# Arduino.net
KiCad netlist of a schematic drawn in EAGLE
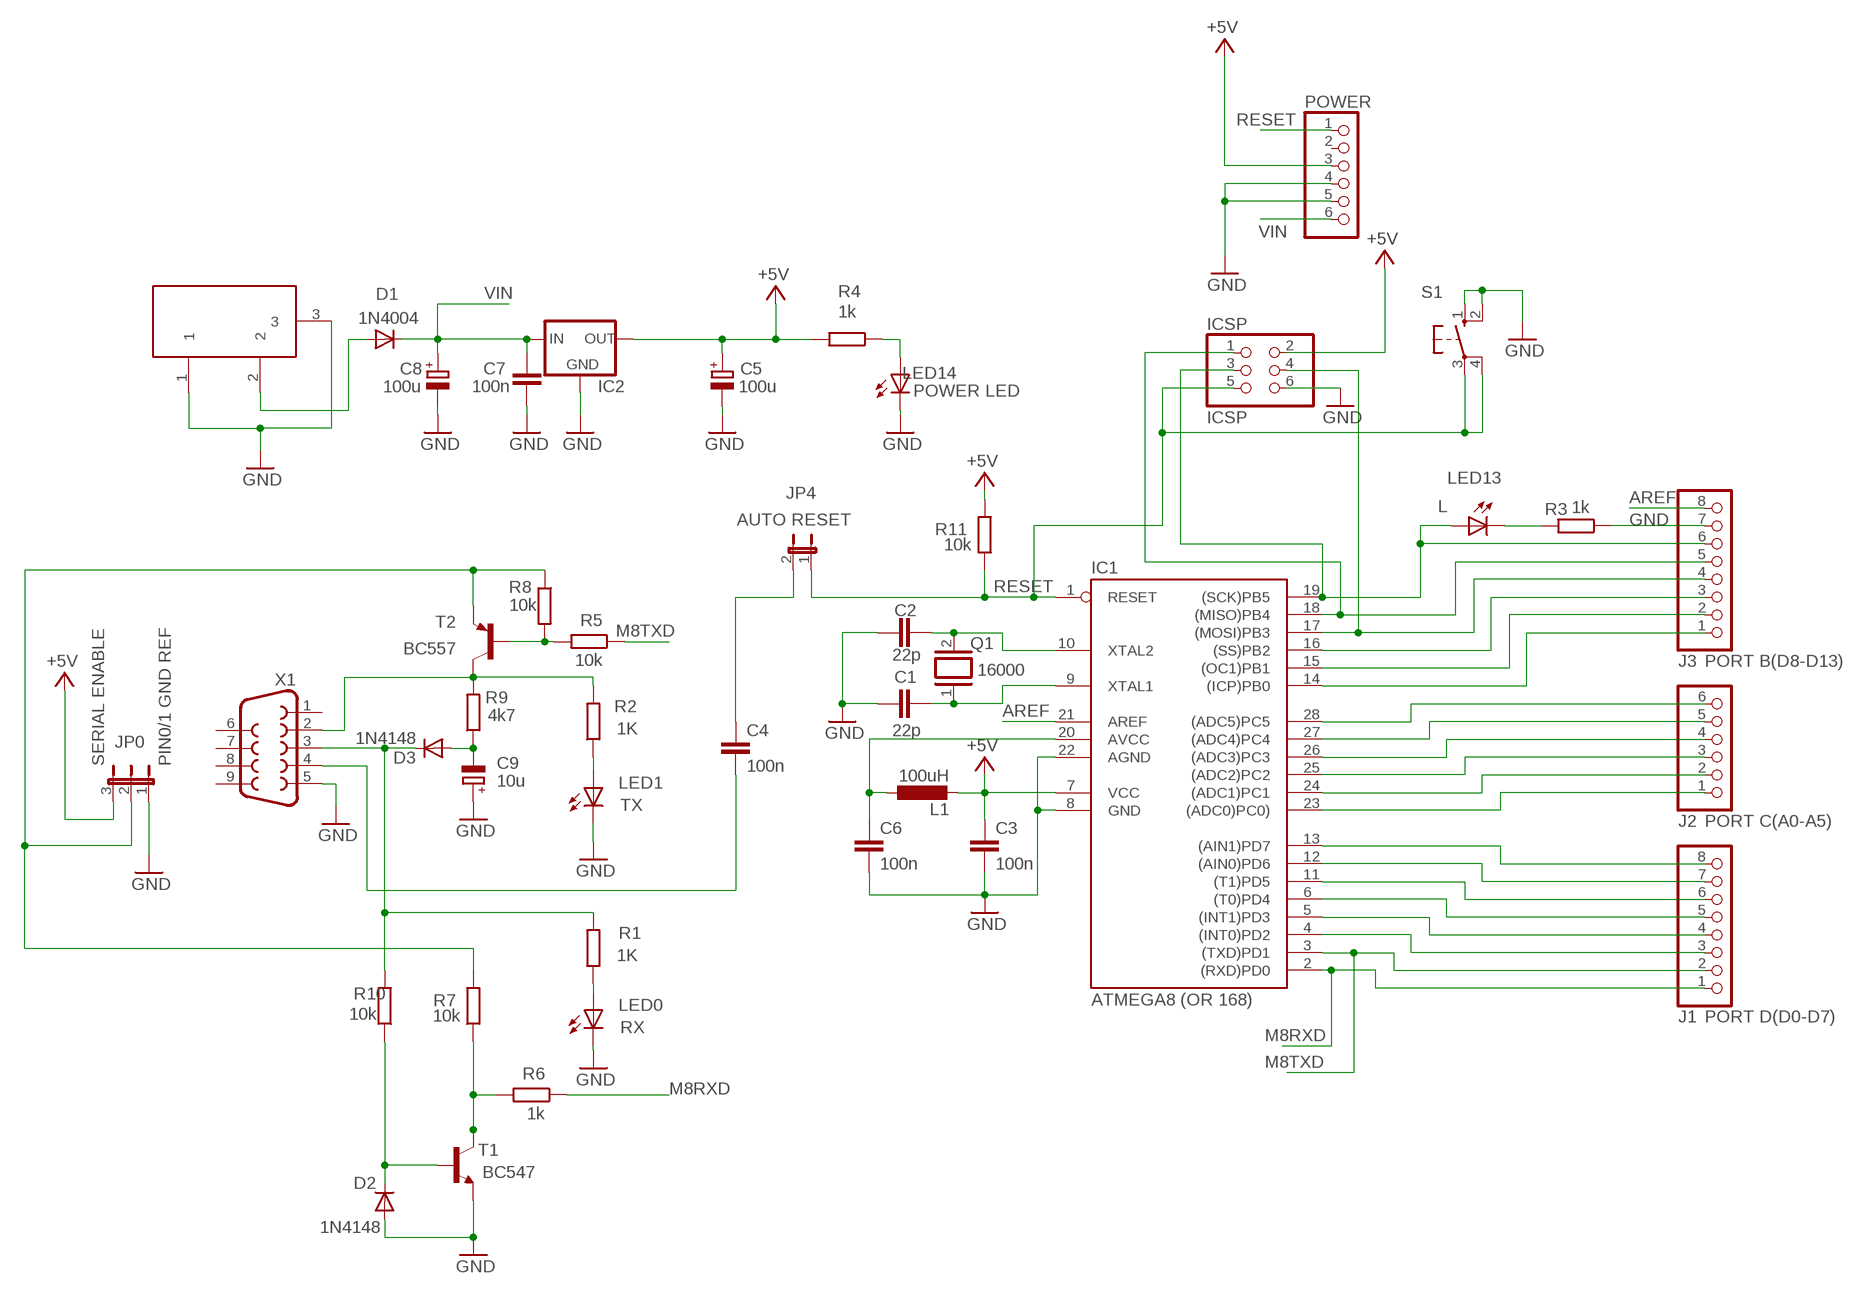
[diagram p0: schematic, sheet 1]

(export (version "E")
  (design (tool "Eeschema 10.0.6"))
  (components
    (comp (ref "C1")
      (value "22p")
      (footprint "eagle-import:C050-025X075")
      (libsource (lib "eagle-import") (part "C-EU050-025X075"))
    )
    (comp (ref "C2")
      (value "22p")
      (footprint "eagle-import:C050-025X075")
      (libsource (lib "eagle-import") (part "C-EU050-025X075"))
    )
    (comp (ref "C3")
      (value "100n")
      (footprint "eagle-import:C050-025X075")
      (libsource (lib "eagle-import") (part "C-EU050-025X075"))
    )
    (comp (ref "C4")
      (value "100n")
      (footprint "eagle-import:C050-025X075")
      (libsource (lib "eagle-import") (part "C-EU050-025X075"))
    )
    (comp (ref "C5")
      (value "100u")
      (footprint "eagle-import:E3,5-8")
      (libsource (lib "eagle-import") (part "CPOL-EUE3.5-8"))
    )
    (comp (ref "C6")
      (value "100n")
      (footprint "eagle-import:C050-025X075")
      (libsource (lib "eagle-import") (part "C-EU050-025X075"))
    )
    (comp (ref "C7")
      (value "100n")
      (footprint "eagle-import:C050-025X075")
      (libsource (lib "eagle-import") (part "C-EU050-025X075"))
    )
    (comp (ref "C8")
      (value "100u")
      (footprint "eagle-import:E3,5-8")
      (libsource (lib "eagle-import") (part "CPOL-EUE3.5-8"))
    )
    (comp (ref "C9")
      (value "10u")
      (footprint "eagle-import:E5-6")
      (libsource (lib "eagle-import") (part "CPOL-EUE5-6"))
    )
    (comp (ref "D1")
      (value "1N4004")
      (footprint "eagle-import:DO41-10")
      (libsource (lib "eagle-import") (part "1N4004"))
    )
    (comp (ref "D2")
      (value "1N4148")
      (footprint "eagle-import:DO35-10")
      (libsource (lib "eagle-import") (part "1N4148"))
    )
    (comp (ref "D3")
      (value "1N4148")
      (footprint "eagle-import:DO35-10")
      (libsource (lib "eagle-import") (part "1N4148"))
    )
    (comp (ref "DC1")
      (value "DC21MMX")
      (footprint "eagle-import:DC-21MM")
      (libsource (lib "eagle-import") (part "DC21MMX"))
    )
    (comp (ref "IC1")
      (value "ATMEGA8 (OR 168)")
      (footprint "eagle-import:DIL28-3")
      (libsource (lib "eagle-import") (part "AT90S4433P"))
    )
    (comp (ref "IC2")
      (value "78XXL")
      (footprint "eagle-import:78XXL")
      (libsource (lib "eagle-import") (part "78XXL"))
    )
    (comp (ref "ICSP")
      (value "ICSP")
      (footprint "eagle-import:2X03")
      (libsource (lib "eagle-import") (part "PINHD-2X3"))
    )
    (comp (ref "J1")
      (value "PORT D(D0-D7)")
      (footprint "eagle-import:1X08")
      (libsource (lib "eagle-import") (part "PINHD-1X8"))
    )
    (comp (ref "J2")
      (value "PORT C(A0-A5)")
      (footprint "eagle-import:1X06")
      (libsource (lib "eagle-import") (part "PINHD-1X6"))
    )
    (comp (ref "J3")
      (value "PORT B(D8-D13)")
      (footprint "eagle-import:1X08")
      (libsource (lib "eagle-import") (part "PINHD-1X8"))
    )
    (comp (ref "JP0")
      (value "JP2W")
      (footprint "eagle-import:JP2W")
      (libsource (lib "eagle-import") (part "JP2W"))
    )
    (comp (ref "JP4")
      (value "AUTO RESET")
      (footprint "eagle-import:JP1W")
      (libsource (lib "eagle-import") (part "JP1W"))
    )
    (comp (ref "L1")
      (value "100uH")
      (footprint "eagle-import:0207_10")
      (libsource (lib "eagle-import") (part "L-EU0207/10"))
    )
    (comp (ref "LED0")
      (value "RX")
      (footprint "eagle-import:LED3MM")
      (libsource (lib "eagle-import") (part "LED3MM"))
    )
    (comp (ref "LED1")
      (value "TX")
      (footprint "eagle-import:LED3MM")
      (libsource (lib "eagle-import") (part "LED3MM"))
    )
    (comp (ref "LED13")
      (value "L")
      (footprint "eagle-import:LED3MM")
      (libsource (lib "eagle-import") (part "LED3MM"))
    )
    (comp (ref "LED14")
      (value "POWER LED")
      (footprint "eagle-import:LED3MM")
      (libsource (lib "eagle-import") (part "LED3MM"))
    )
    (comp (ref "POWER")
      (value "PINHD-1X6")
      (footprint "eagle-import:1X06")
      (libsource (lib "eagle-import") (part "PINHD-1X6"))
    )
    (comp (ref "Q1")
      (value "16000")
      (footprint "eagle-import:Q")
      (libsource (lib "eagle-import") (part "XTAL"))
    )
    (comp (ref "R1")
      (value "1K")
      (footprint "eagle-import:0207_10")
      (libsource (lib "eagle-import") (part "R-EU_0207/10"))
    )
    (comp (ref "R2")
      (value "1K")
      (footprint "eagle-import:0207_10")
      (libsource (lib "eagle-import") (part "R-EU_0207/10"))
    )
    (comp (ref "R3")
      (value "1k")
      (footprint "eagle-import:0207_10")
      (libsource (lib "eagle-import") (part "R-EU_0207/10"))
    )
    (comp (ref "R4")
      (value "1k")
      (footprint "eagle-import:0207_10")
      (libsource (lib "eagle-import") (part "R-EU_0207/10"))
    )
    (comp (ref "R5")
      (value "10k")
      (footprint "eagle-import:0207_10")
      (libsource (lib "eagle-import") (part "R-EU_0207/10"))
    )
    (comp (ref "R6")
      (value "1k")
      (footprint "eagle-import:0207_10")
      (libsource (lib "eagle-import") (part "R-EU_0207/10"))
    )
    (comp (ref "R7")
      (value "10k")
      (footprint "eagle-import:0207_10")
      (libsource (lib "eagle-import") (part "R-EU_0207/10"))
    )
    (comp (ref "R8")
      (value "10k")
      (footprint "eagle-import:0207_10")
      (libsource (lib "eagle-import") (part "R-EU_0207/10"))
    )
    (comp (ref "R9")
      (value "4k7")
      (footprint "eagle-import:0207_10")
      (libsource (lib "eagle-import") (part "R-EU_0207/10"))
    )
    (comp (ref "R10")
      (value "10k")
      (footprint "eagle-import:0207_10")
      (libsource (lib "eagle-import") (part "R-EU_0207/10"))
    )
    (comp (ref "R11")
      (value "10k")
      (footprint "eagle-import:0207_10")
      (libsource (lib "eagle-import") (part "R-EU_0207/10"))
    )
    (comp (ref "S1")
      (value "10-XX")
      (footprint "eagle-import:B3F-10XX")
      (libsource (lib "eagle-import") (part "10-XX"))
    )
    (comp (ref "T1")
      (value "BC547")
      (footprint "eagle-import:TO92")
      (libsource (lib "eagle-import") (part "BC547"))
    )
    (comp (ref "T2")
      (value "BC557")
      (footprint "eagle-import:TO92-EBC")
      (libsource (lib "eagle-import") (part "-PNP-TO92-EBCBC557B"))
    )
    (comp (ref "X1")
      (value "F09H")
      (footprint "eagle-import:F09H")
      (libsource (lib "eagle-import") (part "F09H"))
    )
  )
  (nets
    (net (code "1") (name "+5V") (class "Default")
      (node (ref "C3") (pin "1") (pinfunction "1_1") (pintype "passive"))
      (node (ref "C5") (pin "+") (pinfunction "+_+") (pintype "passive"))
      (node (ref "IC1") (pin "7") (pinfunction "VCC_7") (pintype "power_in"))
      (node (ref "IC2") (pin "OUT") (pinfunction "OUT_OUT") (pintype "passive"))
      (node (ref "ICSP") (pin "2") (pinfunction "2_2") (pintype "passive"))
      (node (ref "JP0") (pin "3") (pinfunction "3_3") (pintype "passive"))
      (node (ref "L1") (pin "2") (pinfunction "2_2") (pintype "passive"))
      (node (ref "POWER") (pin "3") (pinfunction "3_3") (pintype "passive"))
      (node (ref "R11") (pin "2") (pinfunction "2_2") (pintype "passive"))
      (node (ref "R4") (pin "2") (pinfunction "2_2") (pintype "passive"))
    )
    (net (code "2") (name "/AREF") (class "Default")
      (node (ref "IC1") (pin "21") (pinfunction "AREF_21") (pintype "power_in"))
      (node (ref "J3") (pin "8") (pinfunction "8_8") (pintype "passive"))
    )
    (net (code "3") (name "/M8RXD") (class "Default")
      (node (ref "IC1") (pin "2") (pinfunction "(RXD)PD0_2") (pintype "bidirectional"))
      (node (ref "J1") (pin "1") (pinfunction "1_1") (pintype "passive"))
      (node (ref "R6") (pin "1") (pinfunction "1_1") (pintype "passive"))
    )
    (net (code "4") (name "/M8TXD") (class "Default")
      (node (ref "IC1") (pin "3") (pinfunction "(TXD)PD1_3") (pintype "bidirectional"))
      (node (ref "J1") (pin "2") (pinfunction "2_2") (pintype "passive"))
      (node (ref "R5") (pin "1") (pinfunction "1_1") (pintype "passive"))
    )
    (net (code "5") (name "/RESET") (class "Default")
      (node (ref "IC1") (pin "1") (pinfunction "RESET_1") (pintype "input"))
      (node (ref "ICSP") (pin "5") (pinfunction "5_5") (pintype "passive"))
      (node (ref "JP4") (pin "1") (pinfunction "1_1") (pintype "passive"))
      (node (ref "POWER") (pin "1") (pinfunction "1_1") (pintype "passive"))
      (node (ref "R11") (pin "1") (pinfunction "1_1") (pintype "passive"))
      (node (ref "S1") (pin "3") (pinfunction "P_3") (pintype "passive"))
      (node (ref "S1") (pin "4") (pinfunction "P1_4") (pintype "passive"))
    )
    (net (code "6") (name "/VIN") (class "Default")
      (node (ref "C7") (pin "2") (pinfunction "2_2") (pintype "passive"))
      (node (ref "C8") (pin "+") (pinfunction "+_+") (pintype "passive"))
      (node (ref "D1") (pin "C") (pinfunction "C_C") (pintype "passive"))
      (node (ref "IC2") (pin "IN") (pinfunction "IN_IN") (pintype "input"))
      (node (ref "POWER") (pin "6") (pinfunction "6_6") (pintype "passive"))
    )
    (net (code "7") (name "GND") (class "Default")
      (node (ref "C1") (pin "1") (pinfunction "1_1") (pintype "passive"))
      (node (ref "C2") (pin "1") (pinfunction "1_1") (pintype "passive"))
      (node (ref "C3") (pin "2") (pinfunction "2_2") (pintype "passive"))
      (node (ref "C5") (pin "-") (pinfunction "-_-") (pintype "passive"))
      (node (ref "C6") (pin "2") (pinfunction "2_2") (pintype "passive"))
      (node (ref "C7") (pin "1") (pinfunction "1_1") (pintype "passive"))
      (node (ref "C8") (pin "-") (pinfunction "-_-") (pintype "passive"))
      (node (ref "C9") (pin "+") (pinfunction "+_+") (pintype "passive"))
      (node (ref "D2") (pin "A") (pinfunction "A_A") (pintype "passive"))
      (node (ref "DC1") (pin "1") (pinfunction "1_1") (pintype "power_in"))
      (node (ref "DC1") (pin "3") (pinfunction "3_3") (pintype "power_in"))
      (node (ref "IC1") (pin "22") (pinfunction "AGND_22") (pintype "power_in"))
      (node (ref "IC1") (pin "8") (pinfunction "GND_8") (pintype "power_in"))
      (node (ref "IC2") (pin "GND") (pinfunction "GND_GND") (pintype "input"))
      (node (ref "ICSP") (pin "6") (pinfunction "6_6") (pintype "passive"))
      (node (ref "J3") (pin "7") (pinfunction "7_7") (pintype "passive"))
      (node (ref "JP0") (pin "1") (pinfunction "1_1") (pintype "passive"))
      (node (ref "LED0") (pin "K") (pinfunction "C_K") (pintype "passive"))
      (node (ref "LED1") (pin "K") (pinfunction "C_K") (pintype "passive"))
      (node (ref "LED14") (pin "K") (pinfunction "C_K") (pintype "passive"))
      (node (ref "POWER") (pin "4") (pinfunction "4_4") (pintype "passive"))
      (node (ref "POWER") (pin "5") (pinfunction "5_5") (pintype "passive"))
      (node (ref "R3") (pin "1") (pinfunction "1_1") (pintype "passive"))
      (node (ref "S1") (pin "1") (pinfunction "S_1") (pintype "passive"))
      (node (ref "S1") (pin "2") (pinfunction "S1_2") (pintype "passive"))
      (node (ref "T1") (pin "1") (pinfunction "E_1") (pintype "passive"))
      (node (ref "X1") (pin "5") (pinfunction "5_5") (pintype "passive"))
    )
    (net (code "8") (name "Net-(C4-Pad1)") (class "Default")
      (node (ref "C4") (pin "1") (pinfunction "1_1") (pintype "passive"))
      (node (ref "JP4") (pin "2") (pinfunction "2_2") (pintype "passive"))
    )
    (net (code "9") (name "Net-(C4-Pad2)") (class "Default")
      (node (ref "C4") (pin "2") (pinfunction "2_2") (pintype "passive"))
      (node (ref "X1") (pin "4") (pinfunction "4_4") (pintype "passive"))
    )
    (net (code "10") (name "Net-(C9-Pad-)") (class "Default")
      (node (ref "C9") (pin "-") (pinfunction "-_-") (pintype "passive"))
      (node (ref "D3") (pin "A") (pinfunction "A_A") (pintype "passive"))
      (node (ref "R9") (pin "1") (pinfunction "1_1") (pintype "passive"))
    )
    (net (code "11") (name "Net-(D1-PadA)") (class "Default")
      (node (ref "D1") (pin "A") (pinfunction "A_A") (pintype "passive"))
      (node (ref "DC1") (pin "2") (pinfunction "2_2") (pintype "power_in"))
    )
    (net (code "12") (name "Net-(D3-PadC)") (class "Default")
      (node (ref "D3") (pin "C") (pinfunction "C_C") (pintype "passive"))
      (node (ref "R1") (pin "2") (pinfunction "2_2") (pintype "passive"))
      (node (ref "R10") (pin "2") (pinfunction "2_2") (pintype "passive"))
      (node (ref "X1") (pin "3") (pinfunction "3_3") (pintype "passive"))
    )
    (net (code "13") (name "Net-(IC1-(ADC0)PC0))") (class "Default")
      (node (ref "IC1") (pin "23") (pinfunction "(ADC0)PC0)_23") (pintype "bidirectional"))
      (node (ref "J2") (pin "1") (pinfunction "1_1") (pintype "passive"))
    )
    (net (code "14") (name "Net-(IC1-(ADC1)PC1)") (class "Default")
      (node (ref "IC1") (pin "24") (pinfunction "(ADC1)PC1_24") (pintype "bidirectional"))
      (node (ref "J2") (pin "2") (pinfunction "2_2") (pintype "passive"))
    )
    (net (code "15") (name "Net-(IC1-(ADC2)PC2)") (class "Default")
      (node (ref "IC1") (pin "25") (pinfunction "(ADC2)PC2_25") (pintype "bidirectional"))
      (node (ref "J2") (pin "3") (pinfunction "3_3") (pintype "passive"))
    )
    (net (code "16") (name "Net-(IC1-(ADC3)PC3)") (class "Default")
      (node (ref "IC1") (pin "26") (pinfunction "(ADC3)PC3_26") (pintype "bidirectional"))
      (node (ref "J2") (pin "4") (pinfunction "4_4") (pintype "passive"))
    )
    (net (code "17") (name "Net-(IC1-(ADC4)PC4)") (class "Default")
      (node (ref "IC1") (pin "27") (pinfunction "(ADC4)PC4_27") (pintype "bidirectional"))
      (node (ref "J2") (pin "5") (pinfunction "5_5") (pintype "passive"))
    )
    (net (code "18") (name "Net-(IC1-(ADC5)PC5)") (class "Default")
      (node (ref "IC1") (pin "28") (pinfunction "(ADC5)PC5_28") (pintype "bidirectional"))
      (node (ref "J2") (pin "6") (pinfunction "6_6") (pintype "passive"))
    )
    (net (code "19") (name "Net-(IC1-(AIN0)PD6)") (class "Default")
      (node (ref "IC1") (pin "12") (pinfunction "(AIN0)PD6_12") (pintype "bidirectional"))
      (node (ref "J1") (pin "7") (pinfunction "7_7") (pintype "passive"))
    )
    (net (code "20") (name "Net-(IC1-(AIN1)PD7)") (class "Default")
      (node (ref "IC1") (pin "13") (pinfunction "(AIN1)PD7_13") (pintype "bidirectional"))
      (node (ref "J1") (pin "8") (pinfunction "8_8") (pintype "passive"))
    )
    (net (code "21") (name "Net-(IC1-(ICP)PB0)") (class "Default")
      (node (ref "IC1") (pin "14") (pinfunction "(ICP)PB0_14") (pintype "bidirectional"))
      (node (ref "J3") (pin "1") (pinfunction "1_1") (pintype "passive"))
    )
    (net (code "22") (name "Net-(IC1-(INT0)PD2)") (class "Default")
      (node (ref "IC1") (pin "4") (pinfunction "(INT0)PD2_4") (pintype "bidirectional"))
      (node (ref "J1") (pin "3") (pinfunction "3_3") (pintype "passive"))
    )
    (net (code "23") (name "Net-(IC1-(INT1)PD3)") (class "Default")
      (node (ref "IC1") (pin "5") (pinfunction "(INT1)PD3_5") (pintype "bidirectional"))
      (node (ref "J1") (pin "4") (pinfunction "4_4") (pintype "passive"))
    )
    (net (code "24") (name "Net-(IC1-(MISO)PB4)") (class "Default")
      (node (ref "IC1") (pin "18") (pinfunction "(MISO)PB4_18") (pintype "bidirectional"))
      (node (ref "ICSP") (pin "1") (pinfunction "1_1") (pintype "passive"))
      (node (ref "J3") (pin "5") (pinfunction "5_5") (pintype "passive"))
    )
    (net (code "25") (name "Net-(IC1-(MOSI)PB3)") (class "Default")
      (node (ref "IC1") (pin "17") (pinfunction "(MOSI)PB3_17") (pintype "bidirectional"))
      (node (ref "ICSP") (pin "4") (pinfunction "4_4") (pintype "passive"))
      (node (ref "J3") (pin "4") (pinfunction "4_4") (pintype "passive"))
    )
    (net (code "26") (name "Net-(IC1-(OC1)PB1)") (class "Default")
      (node (ref "IC1") (pin "15") (pinfunction "(OC1)PB1_15") (pintype "bidirectional"))
      (node (ref "J3") (pin "2") (pinfunction "2_2") (pintype "passive"))
    )
    (net (code "27") (name "Net-(IC1-(SCK)PB5)") (class "Default")
      (node (ref "IC1") (pin "19") (pinfunction "(SCK)PB5_19") (pintype "bidirectional"))
      (node (ref "ICSP") (pin "3") (pinfunction "3_3") (pintype "passive"))
      (node (ref "J3") (pin "6") (pinfunction "6_6") (pintype "passive"))
      (node (ref "LED13") (pin "A") (pinfunction "A_A") (pintype "passive"))
    )
    (net (code "28") (name "Net-(IC1-(SS)PB2)") (class "Default")
      (node (ref "IC1") (pin "16") (pinfunction "(SS)PB2_16") (pintype "bidirectional"))
      (node (ref "J3") (pin "3") (pinfunction "3_3") (pintype "passive"))
    )
    (net (code "29") (name "Net-(IC1-(T0)PD4)") (class "Default")
      (node (ref "IC1") (pin "6") (pinfunction "(T0)PD4_6") (pintype "bidirectional"))
      (node (ref "J1") (pin "5") (pinfunction "5_5") (pintype "passive"))
    )
    (net (code "30") (name "Net-(IC1-(T1)PD5)") (class "Default")
      (node (ref "IC1") (pin "11") (pinfunction "(T1)PD5_11") (pintype "bidirectional"))
      (node (ref "J1") (pin "6") (pinfunction "6_6") (pintype "passive"))
    )
    (net (code "31") (name "Net-(IC1-AVCC)") (class "Default")
      (node (ref "C6") (pin "1") (pinfunction "1_1") (pintype "passive"))
      (node (ref "IC1") (pin "20") (pinfunction "AVCC_20") (pintype "power_in"))
      (node (ref "L1") (pin "1") (pinfunction "1_1") (pintype "passive"))
    )
    (net (code "32") (name "Net-(IC1-XTAL1)") (class "Default")
      (node (ref "C1") (pin "2") (pinfunction "2_2") (pintype "passive"))
      (node (ref "IC1") (pin "9") (pinfunction "XTAL1_9") (pintype "bidirectional"))
      (node (ref "Q1") (pin "1") (pinfunction "1_1") (pintype "passive"))
    )
    (net (code "33") (name "Net-(IC1-XTAL2)") (class "Default")
      (node (ref "C2") (pin "2") (pinfunction "2_2") (pintype "passive"))
      (node (ref "IC1") (pin "10") (pinfunction "XTAL2_10") (pintype "bidirectional"))
      (node (ref "Q1") (pin "2") (pinfunction "2_2") (pintype "passive"))
    )
    (net (code "34") (name "Net-(JP0-Pad2)") (class "Default")
      (node (ref "JP0") (pin "2") (pinfunction "2_2") (pintype "passive"))
      (node (ref "R7") (pin "2") (pinfunction "2_2") (pintype "passive"))
      (node (ref "R8") (pin "1") (pinfunction "1_1") (pintype "passive"))
      (node (ref "T2") (pin "E") (pinfunction "E_E") (pintype "passive"))
    )
    (net (code "35") (name "Net-(LED0-PadA)") (class "Default")
      (node (ref "LED0") (pin "A") (pinfunction "A_A") (pintype "passive"))
      (node (ref "R1") (pin "1") (pinfunction "1_1") (pintype "passive"))
    )
    (net (code "36") (name "Net-(LED1-PadA)") (class "Default")
      (node (ref "LED1") (pin "A") (pinfunction "A_A") (pintype "passive"))
      (node (ref "R2") (pin "1") (pinfunction "1_1") (pintype "passive"))
    )
    (net (code "37") (name "Net-(LED13-C)") (class "Default")
      (node (ref "LED13") (pin "K") (pinfunction "C_K") (pintype "passive"))
      (node (ref "R3") (pin "2") (pinfunction "2_2") (pintype "passive"))
    )
    (net (code "38") (name "Net-(LED14-PadA)") (class "Default")
      (node (ref "LED14") (pin "A") (pinfunction "A_A") (pintype "passive"))
      (node (ref "R4") (pin "1") (pinfunction "1_1") (pintype "passive"))
    )
    (net (code "39") (name "Net-(R2-Pad2)") (class "Default")
      (node (ref "R2") (pin "2") (pinfunction "2_2") (pintype "passive"))
      (node (ref "R9") (pin "2") (pinfunction "2_2") (pintype "passive"))
      (node (ref "T2") (pin "C") (pinfunction "C_C") (pintype "passive"))
      (node (ref "X1") (pin "2") (pinfunction "2_2") (pintype "passive"))
    )
    (net (code "40") (name "Net-(R5-Pad2)") (class "Default")
      (node (ref "R5") (pin "2") (pinfunction "2_2") (pintype "passive"))
      (node (ref "R8") (pin "2") (pinfunction "2_2") (pintype "passive"))
      (node (ref "T2") (pin "B") (pinfunction "B_B") (pintype "passive"))
    )
    (net (code "41") (name "Net-(T1-B)") (class "Default")
      (node (ref "D2") (pin "C") (pinfunction "C_C") (pintype "passive"))
      (node (ref "R10") (pin "1") (pinfunction "1_1") (pintype "passive"))
      (node (ref "T1") (pin "2") (pinfunction "B_2") (pintype "passive"))
    )
    (net (code "42") (name "Net-(T1-C)") (class "Default")
      (node (ref "R6") (pin "2") (pinfunction "2_2") (pintype "passive"))
      (node (ref "R7") (pin "1") (pinfunction "1_1") (pintype "passive"))
      (node (ref "T1") (pin "3") (pinfunction "C_3") (pintype "passive"))
    )
    (net (code "43") (name "unconnected-(POWER-Pad2)") (class "Default")
      (node (ref "POWER") (pin "2") (pinfunction "2_2") (pintype "passive"))
    )
    (net (code "44") (name "unconnected-(X1-Pad1)") (class "Default")
      (node (ref "X1") (pin "1") (pinfunction "1_1") (pintype "passive"))
    )
    (net (code "45") (name "unconnected-(X1-Pad6)") (class "Default")
      (node (ref "X1") (pin "6") (pinfunction "6_6") (pintype "passive"))
    )
    (net (code "46") (name "unconnected-(X1-Pad7)") (class "Default")
      (node (ref "X1") (pin "7") (pinfunction "7_7") (pintype "passive"))
    )
    (net (code "47") (name "unconnected-(X1-Pad8)") (class "Default")
      (node (ref "X1") (pin "8") (pinfunction "8_8") (pintype "passive"))
    )
    (net (code "48") (name "unconnected-(X1-Pad9)") (class "Default")
      (node (ref "X1") (pin "9") (pinfunction "9_9") (pintype "passive"))
    )
  )
)
